# Light_Schematic.net
KiCad netlist of a schematic drawn in EAGLE
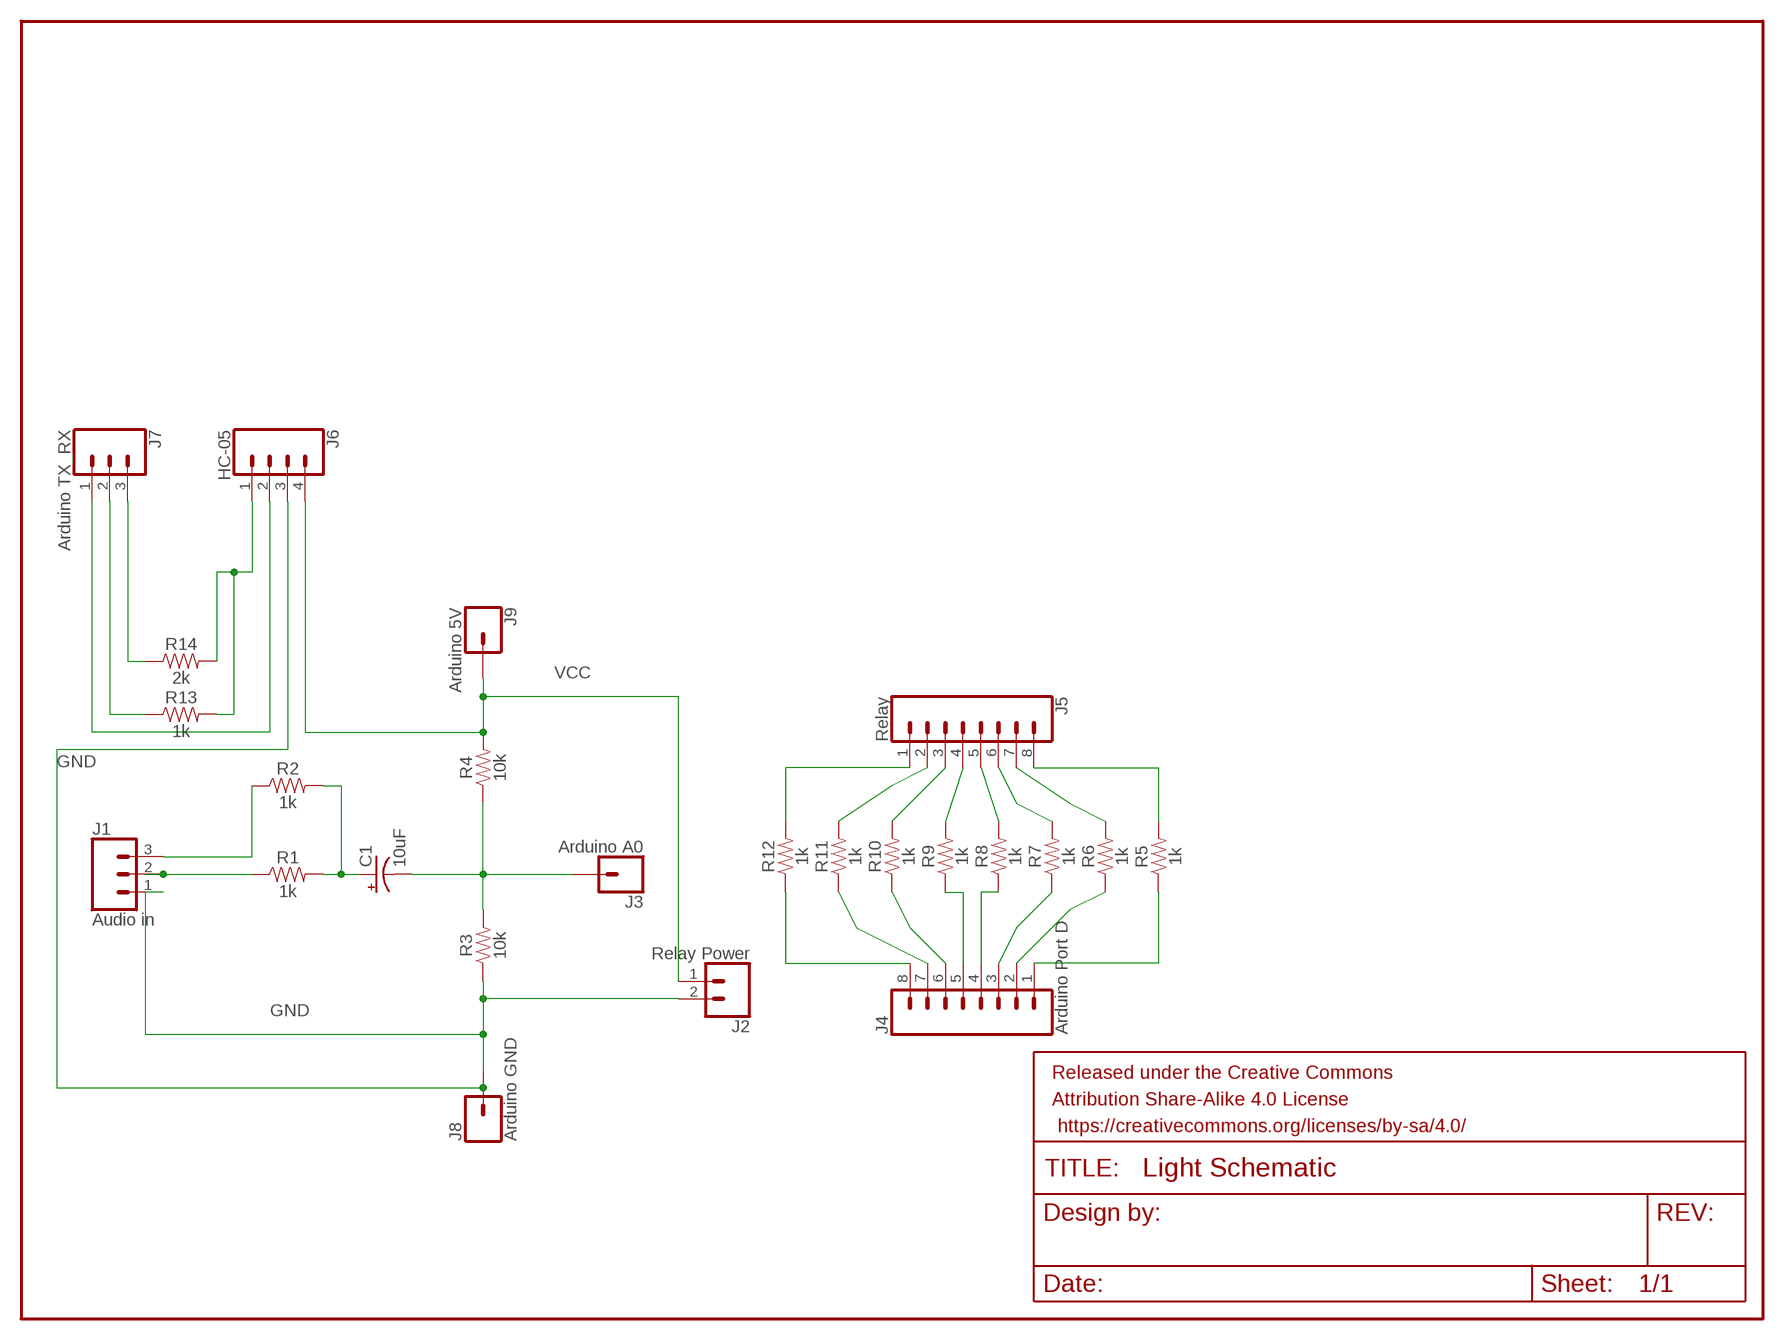
[diagram p0: schematic, sheet 1]

(export (version "E")
  (design (tool "Eeschema 10.0.6"))
  (components
    (comp (ref "C1")
      (value "10uF")
      (footprint "eagle-import:CPOL-RADIAL-2.5MM-5MM")
      (libsource (lib "eagle-import") (part "10UF-POLAR-RADIAL-2.5MM-25V-20%"))
    )
    (comp (ref "FRAME1")
      (value "FRAME-LETTER")
      (footprint "eagle-import:CREATIVE_COMMONS")
      (libsource (lib "eagle-import") (part "FRAME-LETTER"))
    )
    (comp (ref "J1")
      (value "Audio in")
      (footprint "eagle-import:1X03")
      (libsource (lib "eagle-import") (part "CONN_03"))
    )
    (comp (ref "J2")
      (value "Relay Power")
      (footprint "eagle-import:1X02")
      (libsource (lib "eagle-import") (part "CONN_02"))
    )
    (comp (ref "J3")
      (value "Arduino A0")
      (footprint "eagle-import:1X01")
      (libsource (lib "eagle-import") (part "CONN_01"))
    )
    (comp (ref "J4")
      (value "Arduino Port D")
      (footprint "eagle-import:1X08")
      (libsource (lib "eagle-import") (part "CONN_08{dblquote}"))
    )
    (comp (ref "J5")
      (value "Relay")
      (footprint "eagle-import:1X08")
      (libsource (lib "eagle-import") (part "CONN_08{dblquote}"))
    )
    (comp (ref "J6")
      (value "HC-05")
      (footprint "eagle-import:1X04")
      (libsource (lib "eagle-import") (part "CONN_04"))
    )
    (comp (ref "J7")
      (value "Arduino TX_RX")
      (footprint "eagle-import:1X03")
      (libsource (lib "eagle-import") (part "CONN_03"))
    )
    (comp (ref "J8")
      (value "Arduino GND")
      (footprint "eagle-import:1X01")
      (libsource (lib "eagle-import") (part "CONN_01"))
    )
    (comp (ref "J9")
      (value "Arduino 5V")
      (footprint "eagle-import:1X01")
      (libsource (lib "eagle-import") (part "CONN_01"))
    )
    (comp (ref "R1")
      (value "1k")
      (footprint "eagle-import:AXIAL-0.3")
      (libsource (lib "eagle-import") (part "1KOHM-HORIZ-1/4W-5%"))
    )
    (comp (ref "R2")
      (value "1k")
      (footprint "eagle-import:AXIAL-0.3")
      (libsource (lib "eagle-import") (part "1KOHM-HORIZ-1/4W-5%"))
    )
    (comp (ref "R3")
      (value "10k")
      (footprint "eagle-import:AXIAL-0.3")
      (libsource (lib "eagle-import") (part "10KOHM-HORIZ-1/6W-5%"))
    )
    (comp (ref "R4")
      (value "10k")
      (footprint "eagle-import:AXIAL-0.3")
      (libsource (lib "eagle-import") (part "10KOHM-HORIZ-1/6W-5%"))
    )
    (comp (ref "R5")
      (value "1k")
      (footprint "eagle-import:AXIAL-0.3")
      (libsource (lib "eagle-import") (part "1KOHM-HORIZ-1/4W-5%"))
    )
    (comp (ref "R6")
      (value "1k")
      (footprint "eagle-import:AXIAL-0.3")
      (libsource (lib "eagle-import") (part "1KOHM-HORIZ-1/4W-5%"))
    )
    (comp (ref "R7")
      (value "1k")
      (footprint "eagle-import:AXIAL-0.3")
      (libsource (lib "eagle-import") (part "1KOHM-HORIZ-1/4W-5%"))
    )
    (comp (ref "R8")
      (value "1k")
      (footprint "eagle-import:AXIAL-0.3")
      (libsource (lib "eagle-import") (part "1KOHM-HORIZ-1/4W-5%"))
    )
    (comp (ref "R9")
      (value "1k")
      (footprint "eagle-import:AXIAL-0.3")
      (libsource (lib "eagle-import") (part "1KOHM-HORIZ-1/4W-5%"))
    )
    (comp (ref "R10")
      (value "1k")
      (footprint "eagle-import:AXIAL-0.3")
      (libsource (lib "eagle-import") (part "1KOHM-HORIZ-1/4W-5%"))
    )
    (comp (ref "R11")
      (value "1k")
      (footprint "eagle-import:AXIAL-0.3")
      (libsource (lib "eagle-import") (part "1KOHM-HORIZ-1/4W-5%"))
    )
    (comp (ref "R12")
      (value "1k")
      (footprint "eagle-import:AXIAL-0.3")
      (libsource (lib "eagle-import") (part "1KOHM-HORIZ-1/4W-5%"))
    )
    (comp (ref "R13")
      (value "1k")
      (footprint "eagle-import:AXIAL-0.3")
      (libsource (lib "eagle-import") (part "1KOHM-HORIZ-1/4W-5%"))
    )
    (comp (ref "R14")
      (value "2k")
      (footprint "eagle-import:AXIAL-0.3")
      (libsource (lib "eagle-import") (part "1KOHM-HORIZ-1/4W-1%"))
    )
  )
  (nets
    (net (code "1") (name "/GND") (class "Default")
      (node (ref "J1") (pin "1") (pinfunction "1_1") (pintype "passive"))
      (node (ref "J2") (pin "2") (pinfunction "2_2") (pintype "passive"))
      (node (ref "J6") (pin "3") (pinfunction "3_3") (pintype "passive"))
      (node (ref "J8") (pin "1") (pinfunction "1_1") (pintype "passive"))
      (node (ref "R3") (pin "P$1") (pinfunction "1_P$1") (pintype "passive"))
    )
    (net (code "2") (name "/R1") (class "Default")
      (node (ref "J4") (pin "8") (pinfunction "8_8") (pintype "passive"))
      (node (ref "J5") (pin "1") (pinfunction "1_1") (pintype "passive"))
      (node (ref "R12") (pin "P$1") (pinfunction "1_P$1") (pintype "passive"))
      (node (ref "R12") (pin "P$2") (pinfunction "2_P$2") (pintype "passive"))
    )
    (net (code "3") (name "/R2") (class "Default")
      (node (ref "J4") (pin "7") (pinfunction "7_7") (pintype "passive"))
      (node (ref "J5") (pin "2") (pinfunction "2_2") (pintype "passive"))
      (node (ref "R11") (pin "P$1") (pinfunction "1_P$1") (pintype "passive"))
      (node (ref "R11") (pin "P$2") (pinfunction "2_P$2") (pintype "passive"))
    )
    (net (code "4") (name "/R3") (class "Default")
      (node (ref "J4") (pin "6") (pinfunction "6_6") (pintype "passive"))
      (node (ref "J5") (pin "3") (pinfunction "3_3") (pintype "passive"))
      (node (ref "R10") (pin "P$1") (pinfunction "1_P$1") (pintype "passive"))
      (node (ref "R10") (pin "P$2") (pinfunction "2_P$2") (pintype "passive"))
    )
    (net (code "5") (name "/R4") (class "Default")
      (node (ref "J4") (pin "5") (pinfunction "5_5") (pintype "passive"))
      (node (ref "J5") (pin "4") (pinfunction "4_4") (pintype "passive"))
      (node (ref "R9") (pin "P$1") (pinfunction "1_P$1") (pintype "passive"))
      (node (ref "R9") (pin "P$2") (pinfunction "2_P$2") (pintype "passive"))
    )
    (net (code "6") (name "/R5") (class "Default")
      (node (ref "J4") (pin "4") (pinfunction "4_4") (pintype "passive"))
      (node (ref "J5") (pin "5") (pinfunction "5_5") (pintype "passive"))
      (node (ref "R8") (pin "P$1") (pinfunction "1_P$1") (pintype "passive"))
      (node (ref "R8") (pin "P$2") (pinfunction "2_P$2") (pintype "passive"))
    )
    (net (code "7") (name "/VCC") (class "Default")
      (node (ref "J2") (pin "1") (pinfunction "1_1") (pintype "passive"))
      (node (ref "J6") (pin "4") (pinfunction "4_4") (pintype "passive"))
      (node (ref "J9") (pin "1") (pinfunction "1_1") (pintype "passive"))
      (node (ref "R4") (pin "P$2") (pinfunction "2_P$2") (pintype "passive"))
    )
    (net (code "8") (name "Net-(C1-+)") (class "Default")
      (node (ref "C1") (pin "1") (pinfunction "+_1") (pintype "passive"))
      (node (ref "R1") (pin "P$2") (pinfunction "2_P$2") (pintype "passive"))
      (node (ref "R2") (pin "P$2") (pinfunction "2_P$2") (pintype "passive"))
    )
    (net (code "9") (name "Net-(C1--)") (class "Default")
      (node (ref "C1") (pin "2") (pinfunction "-_2") (pintype "passive"))
      (node (ref "J3") (pin "1") (pinfunction "1_1") (pintype "passive"))
      (node (ref "R3") (pin "P$2") (pinfunction "2_P$2") (pintype "passive"))
      (node (ref "R4") (pin "P$1") (pinfunction "1_P$1") (pintype "passive"))
    )
    (net (code "10") (name "Net-(J6-Pad2)") (class "Default")
      (node (ref "J6") (pin "2") (pinfunction "2_2") (pintype "passive"))
      (node (ref "J7") (pin "1") (pinfunction "1_1") (pintype "passive"))
    )
    (net (code "11") (name "Net-(R1-1)") (class "Default")
      (node (ref "J1") (pin "2") (pinfunction "2_2") (pintype "passive"))
      (node (ref "R1") (pin "P$1") (pinfunction "1_P$1") (pintype "passive"))
    )
    (net (code "12") (name "Net-(R2-1)") (class "Default")
      (node (ref "J1") (pin "3") (pinfunction "3_3") (pintype "passive"))
      (node (ref "R2") (pin "P$1") (pinfunction "1_P$1") (pintype "passive"))
    )
    (net (code "13") (name "Net-(R5-1)") (class "Default")
      (node (ref "J4") (pin "1") (pinfunction "1_1") (pintype "passive"))
      (node (ref "R5") (pin "P$1") (pinfunction "1_P$1") (pintype "passive"))
    )
    (net (code "14") (name "Net-(R5-2)") (class "Default")
      (node (ref "J5") (pin "8") (pinfunction "8_8") (pintype "passive"))
      (node (ref "R5") (pin "P$2") (pinfunction "2_P$2") (pintype "passive"))
    )
    (net (code "15") (name "Net-(R6-1)") (class "Default")
      (node (ref "J4") (pin "2") (pinfunction "2_2") (pintype "passive"))
      (node (ref "R6") (pin "P$1") (pinfunction "1_P$1") (pintype "passive"))
    )
    (net (code "16") (name "Net-(R6-2)") (class "Default")
      (node (ref "J5") (pin "7") (pinfunction "7_7") (pintype "passive"))
      (node (ref "R6") (pin "P$2") (pinfunction "2_P$2") (pintype "passive"))
    )
    (net (code "17") (name "Net-(R7-1)") (class "Default")
      (node (ref "J4") (pin "3") (pinfunction "3_3") (pintype "passive"))
      (node (ref "R7") (pin "P$1") (pinfunction "1_P$1") (pintype "passive"))
    )
    (net (code "18") (name "Net-(R7-2)") (class "Default")
      (node (ref "J5") (pin "6") (pinfunction "6_6") (pintype "passive"))
      (node (ref "R7") (pin "P$2") (pinfunction "2_P$2") (pintype "passive"))
    )
    (net (code "19") (name "Net-(R13-1)") (class "Default")
      (node (ref "J7") (pin "2") (pinfunction "2_2") (pintype "passive"))
      (node (ref "R13") (pin "P$1") (pinfunction "1_P$1") (pintype "passive"))
    )
    (net (code "20") (name "Net-(R13-2)") (class "Default")
      (node (ref "J6") (pin "1") (pinfunction "1_1") (pintype "passive"))
      (node (ref "R13") (pin "P$2") (pinfunction "2_P$2") (pintype "passive"))
      (node (ref "R14") (pin "P$2") (pinfunction "2_P$2") (pintype "passive"))
    )
    (net (code "21") (name "Net-(R14-1)") (class "Default")
      (node (ref "J7") (pin "3") (pinfunction "3_3") (pintype "passive"))
      (node (ref "R14") (pin "P$1") (pinfunction "1_P$1") (pintype "passive"))
    )
  )
)
